# 600Hz_LO_LPF.net
KiCad netlist of a schematic drawn in Altium Designer
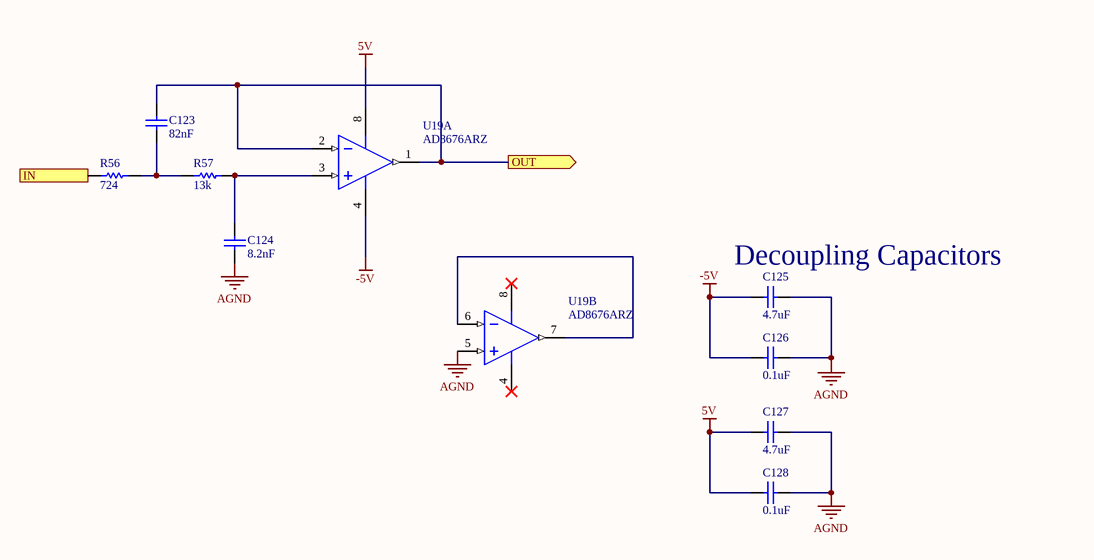
[diagram p0: 600Hz_LO_LPF.SchDoc]

(export (version "E")
  (design (tool "Eeschema 10.0.6"))
  (components
    (comp (ref "C123")
      (value "82nF")
      (footprint "0402_Cap")
      (description "Capacitor, 16nF, 0805, 25V")
      (libsource (lib "Arturo_Approved") (part "08051C163JAT2A"))
    )
    (comp (ref "C124")
      (value "8.2nF")
      (footprint "0402_Cap")
      (description "Capacitor, 1.6nF, 0805, 25V")
      (libsource (lib "Arturo_Approved") (part "GRM2165C2A162JA01D"))
    )
    (comp (ref "C125")
      (value "4.7uF")
      (footprint "0402_Cap")
      (description "Capacitor, 4.7uF, 0805")
      (libsource (lib "Arturo_Approved") (part "CL21A475KAQNNNE"))
    )
    (comp (ref "C126")
      (value "0.1uF")
      (footprint "0402_Cap")
      (description "Capacitor, 0.1uF, 0805")
      (libsource (lib "Arturo_Approved") (part "CL21B104KACNNNC"))
    )
    (comp (ref "C127")
      (value "4.7uF")
      (footprint "0402_Cap")
      (description "Capacitor, 4.7uF, 0805")
      (libsource (lib "Arturo_Approved") (part "CL21A475KAQNNNE"))
    )
    (comp (ref "C128")
      (value "0.1uF")
      (footprint "0402_Cap")
      (description "Capacitor, 0.1uF, 0805")
      (libsource (lib "Arturo_Approved") (part "CL21B104KACNNNC"))
    )
    (comp (ref "R56")
      (value "724")
      (footprint "0402_Res")
      (description "1.65k")
      (libsource (lib "Arturo_Approved") (part "RC0805FR-071K65L"))
    )
    (comp (ref "R57")
      (value "13k")
      (footprint "0402_Res")
      (description "5.9k")
      (libsource (lib "Arturo_Approved") (part "RC0805FR-075K9L"))
    )
    (comp (ref "U19")
      (value "AD8676ARZ")
      (footprint "ADI-R-8_M")
      (fields (field (name "GENERIC PART NUMBER") "AD8676") (field (name "MANUFACTURER") "Analog Devices"))
      (libsource (lib "Altium Content Vault") (part "ADI-OP29X-R-8"))
    )
  )
  (nets
    (net (code "1") (name "-5V") (class "Default")
      (node (ref "C125") (pin "1") (pinfunction "1_1") (pintype "passive"))
      (node (ref "C126") (pin "1") (pinfunction "1_1") (pintype "passive"))
      (node (ref "U19") (pin "4") (pinfunction "-V_4") (pintype "power_in"))
    )
    (net (code "2") (name "/IN") (class "Default")
      (node (ref "R56") (pin "1") (pinfunction "1_1") (pintype "passive"))
    )
    (net (code "3") (name "/OUT") (class "Default")
      (node (ref "C123") (pin "2") (pinfunction "2_2") (pintype "passive"))
      (node (ref "U19") (pin "1") (pinfunction "OUT_A_1") (pintype "output"))
      (node (ref "U19") (pin "2") (pinfunction "-IN_A_2") (pintype "input"))
    )
    (net (code "4") (name "5V") (class "Default")
      (node (ref "C127") (pin "1") (pinfunction "1_1") (pintype "passive"))
      (node (ref "C128") (pin "1") (pinfunction "1_1") (pintype "passive"))
      (node (ref "U19") (pin "8") (pinfunction "+V_8") (pintype "power_in"))
    )
    (net (code "5") (name "AGND") (class "Default")
      (node (ref "C124") (pin "1") (pinfunction "1_1") (pintype "passive"))
      (node (ref "C125") (pin "2") (pinfunction "2_2") (pintype "passive"))
      (node (ref "C126") (pin "2") (pinfunction "2_2") (pintype "passive"))
      (node (ref "C127") (pin "2") (pinfunction "2_2") (pintype "passive"))
      (node (ref "C128") (pin "2") (pinfunction "2_2") (pintype "passive"))
      (node (ref "U19") (pin "5") (pinfunction "+IN_B_5") (pintype "input"))
    )
    (net (code "6") (name "Net-(C123-Pad1)") (class "Default")
      (node (ref "C123") (pin "1") (pinfunction "1_1") (pintype "passive"))
      (node (ref "R56") (pin "2") (pinfunction "2_2") (pintype "passive"))
      (node (ref "R57") (pin "1") (pinfunction "1_1") (pintype "passive"))
    )
    (net (code "7") (name "Net-(U19A-+IN_A)") (class "Default")
      (node (ref "C124") (pin "2") (pinfunction "2_2") (pintype "passive"))
      (node (ref "R57") (pin "2") (pinfunction "2_2") (pintype "passive"))
      (node (ref "U19") (pin "3") (pinfunction "+IN_A_3") (pintype "input"))
    )
    (net (code "8") (name "Net-(U19B--IN_B)") (class "Default")
      (node (ref "U19") (pin "6") (pinfunction "-IN_B_6") (pintype "input"))
      (node (ref "U19") (pin "7") (pinfunction "OUT_B_7") (pintype "output"))
    )
    (net (code "9") (name "unconnected-(U19B-+V-Pad8)") (class "Default")
      (node (ref "U19") (pin "8") (pinfunction "+V_8") (pintype "power_in+no_connect"))
    )
    (net (code "10") (name "unconnected-(U19B--V-Pad4)") (class "Default")
      (node (ref "U19") (pin "4") (pinfunction "-V_4") (pintype "power_in+no_connect"))
    )
  )
)
